# ANALOG.net
KiCad netlist of a schematic drawn in Altium Designer
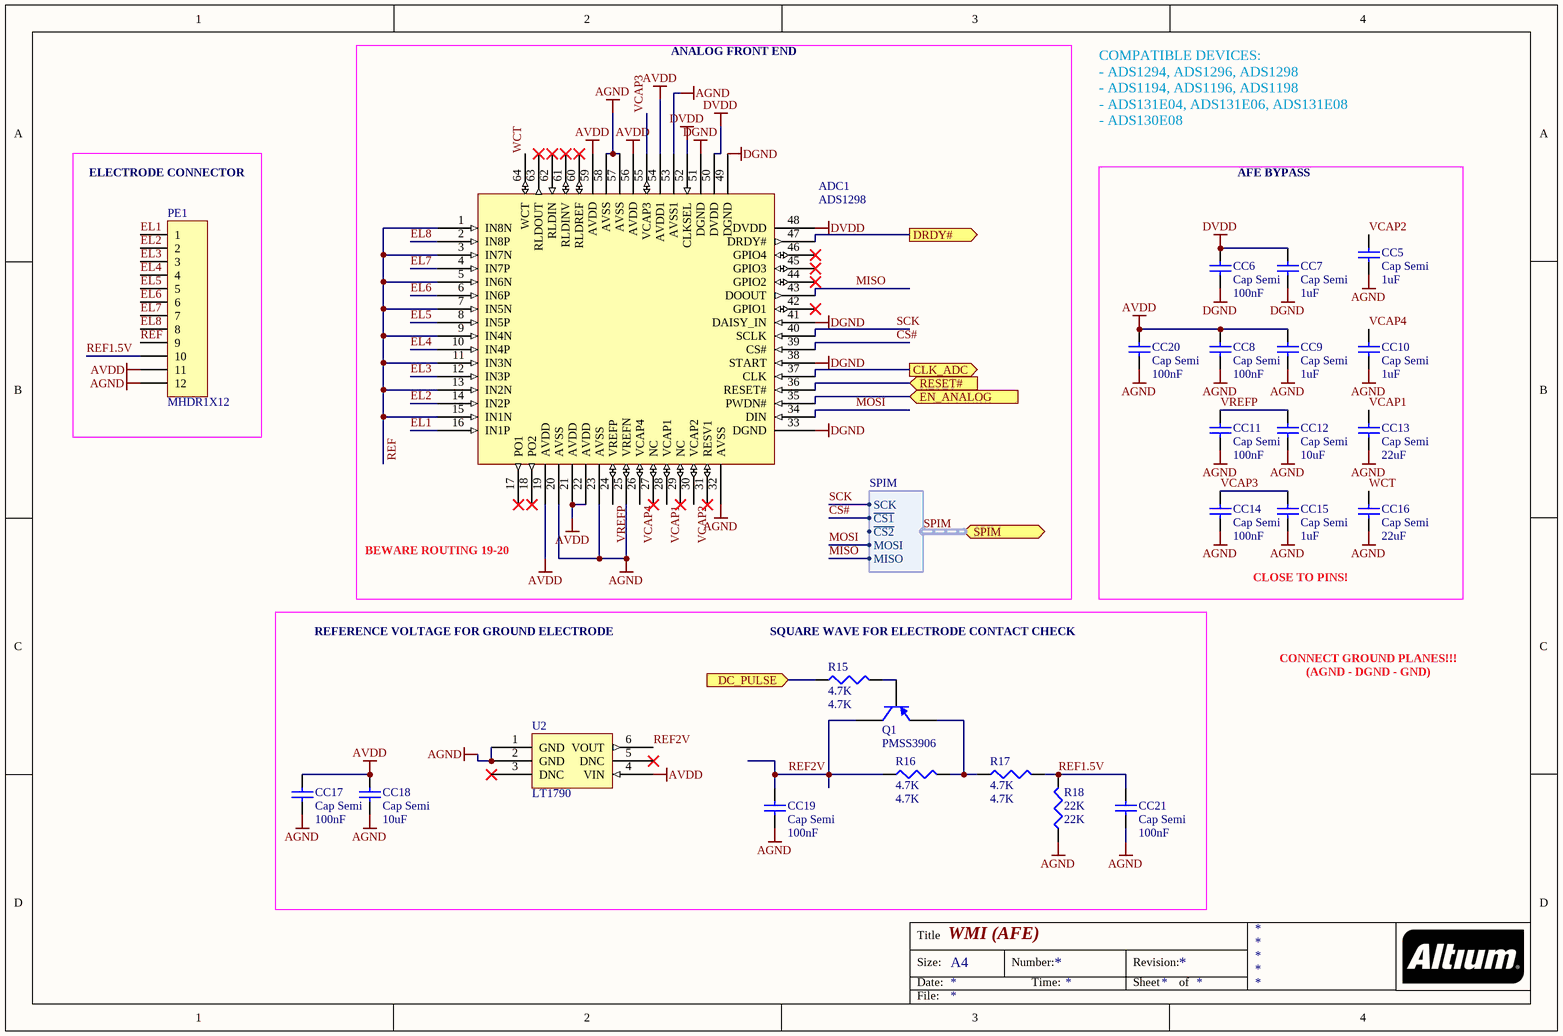
[diagram p0: ANALOG.SchDoc]

(export (version "E")
  (design (tool "Eeschema 10.0.6"))
  (components
    (comp (ref "ADC1")
      (value "ADS1298")
      (footprint "Atmel Microcontroller 32-Bit ARM:LQFP64_M")
      (libsource (lib "Schlib1") (part "ADS1298"))
    )
    (comp (ref "CC5")
      (value "Cap Semi")
      (footprint "0402")
      (description "Capacitor (Semiconductor SIM Model)")
      (fields (field (name "ALTIUM_VALUE") "1uF") (field (name "PUBLISHER") "Altium Limited"))
      (libsource (lib "Miscellaneous Devices") (part "Cap Semi"))
    )
    (comp (ref "CC6")
      (value "Cap Semi")
      (footprint "0402")
      (description "Capacitor (Semiconductor SIM Model)")
      (fields (field (name "ALTIUM_VALUE") "100nF") (field (name "PUBLISHER") "Altium Limited"))
      (libsource (lib "Miscellaneous Devices") (part "Cap Semi"))
    )
    (comp (ref "CC7")
      (value "Cap Semi")
      (footprint "0402")
      (description "Capacitor (Semiconductor SIM Model)")
      (fields (field (name "ALTIUM_VALUE") "1uF") (field (name "PUBLISHER") "Altium Limited"))
      (libsource (lib "Miscellaneous Devices") (part "Cap Semi"))
    )
    (comp (ref "CC8")
      (value "Cap Semi")
      (footprint "0402")
      (description "Capacitor (Semiconductor SIM Model)")
      (fields (field (name "ALTIUM_VALUE") "100nF") (field (name "PUBLISHER") "Altium Limited"))
      (libsource (lib "Miscellaneous Devices") (part "Cap Semi"))
    )
    (comp (ref "CC9")
      (value "Cap Semi")
      (footprint "0402")
      (description "Capacitor (Semiconductor SIM Model)")
      (fields (field (name "ALTIUM_VALUE") "1uF") (field (name "PUBLISHER") "Altium Limited"))
      (libsource (lib "Miscellaneous Devices") (part "Cap Semi"))
    )
    (comp (ref "CC10")
      (value "Cap Semi")
      (footprint "0402")
      (description "Capacitor (Semiconductor SIM Model)")
      (fields (field (name "ALTIUM_VALUE") "1uF") (field (name "PUBLISHER") "Altium Limited"))
      (libsource (lib "Miscellaneous Devices") (part "Cap Semi"))
    )
    (comp (ref "CC11")
      (value "Cap Semi")
      (footprint "0402")
      (description "Capacitor (Semiconductor SIM Model)")
      (fields (field (name "ALTIUM_VALUE") "100nF") (field (name "PUBLISHER") "Altium Limited"))
      (libsource (lib "Miscellaneous Devices") (part "Cap Semi"))
    )
    (comp (ref "CC12")
      (value "Cap Semi")
      (footprint "0402")
      (description "Capacitor (Semiconductor SIM Model)")
      (fields (field (name "ALTIUM_VALUE") "10uF") (field (name "PUBLISHER") "Altium Limited"))
      (libsource (lib "Miscellaneous Devices") (part "Cap Semi"))
    )
    (comp (ref "CC13")
      (value "Cap Semi")
      (footprint "0402")
      (description "Capacitor (Semiconductor SIM Model)")
      (fields (field (name "ALTIUM_VALUE") "22uF") (field (name "PUBLISHER") "Altium Limited"))
      (libsource (lib "Miscellaneous Devices") (part "Cap Semi"))
    )
    (comp (ref "CC14")
      (value "Cap Semi")
      (footprint "0402")
      (description "Capacitor (Semiconductor SIM Model)")
      (fields (field (name "ALTIUM_VALUE") "100nF") (field (name "PUBLISHER") "Altium Limited"))
      (libsource (lib "Miscellaneous Devices") (part "Cap Semi"))
    )
    (comp (ref "CC15")
      (value "Cap Semi")
      (footprint "0402")
      (description "Capacitor (Semiconductor SIM Model)")
      (fields (field (name "ALTIUM_VALUE") "1uF") (field (name "PUBLISHER") "Altium Limited"))
      (libsource (lib "Miscellaneous Devices") (part "Cap Semi"))
    )
    (comp (ref "CC16")
      (value "Cap Semi")
      (footprint "1608[0603]")
      (description "Capacitor (Semiconductor SIM Model)")
      (fields (field (name "ALTIUM_VALUE") "22uF") (field (name "PUBLISHER") "Altium Limited"))
      (libsource (lib "Miscellaneous Devices") (part "Cap Semi"))
    )
    (comp (ref "CC17")
      (value "Cap Semi")
      (footprint "0402")
      (description "Capacitor (Semiconductor SIM Model)")
      (fields (field (name "ALTIUM_VALUE") "100nF") (field (name "PUBLISHER") "Altium Limited"))
      (libsource (lib "Miscellaneous Devices") (part "Cap Semi"))
    )
    (comp (ref "CC18")
      (value "Cap Semi")
      (footprint "0402")
      (description "Capacitor (Semiconductor SIM Model)")
      (fields (field (name "ALTIUM_VALUE") "10uF") (field (name "PUBLISHER") "Altium Limited"))
      (libsource (lib "Miscellaneous Devices") (part "Cap Semi"))
    )
    (comp (ref "CC19")
      (value "Cap Semi")
      (footprint "0402")
      (description "Capacitor (Semiconductor SIM Model)")
      (fields (field (name "ALTIUM_VALUE") "100nF") (field (name "PUBLISHER") "Altium Limited"))
      (libsource (lib "Miscellaneous Devices") (part "Cap Semi"))
    )
    (comp (ref "CC20")
      (value "Cap Semi")
      (footprint "0402")
      (description "Capacitor (Semiconductor SIM Model)")
      (fields (field (name "ALTIUM_VALUE") "100nF") (field (name "PUBLISHER") "Altium Limited"))
      (libsource (lib "Miscellaneous Devices") (part "Cap Semi"))
    )
    (comp (ref "CC21")
      (value "Cap Semi")
      (footprint "0402")
      (description "Capacitor (Semiconductor SIM Model)")
      (fields (field (name "ALTIUM_VALUE") "100nF") (field (name "PUBLISHER") "Altium Limited"))
      (libsource (lib "Miscellaneous Devices") (part "Cap Semi"))
    )
    (comp (ref "PE1")
      (value "MHDR1X12")
      (footprint "HEADER12")
      (description "Header, 12-Pin")
      (fields (field (name "PUBLISHER") "Altium Limited"))
      (libsource (lib "Miscellaneous Connectors") (part "MHDR1X12"))
    )
    (comp (ref "Q1")
      (value "PMSS3906")
      (footprint "SOT323_N")
      (description "PNP Switching Transistor")
      (fields (field (name "PUBLISHER") "Altium Limited"))
      (libsource (lib "Philips Discrete BJT - Low Power") (part "PMSS3906"))
    )
    (comp (ref "R15")
      (value "4.7K")
      (footprint "0402")
      (description "Resistor")
      (fields (field (name "ALTIUM_VALUE") "4.7K") (field (name "PUBLISHER") "Altium Limited"))
      (libsource (lib "Miscellaneous Devices") (part "Res3"))
    )
    (comp (ref "R16")
      (value "4.7K")
      (footprint "0402")
      (description "Resistor")
      (fields (field (name "ALTIUM_VALUE") "4.7K") (field (name "PUBLISHER") "Altium Limited"))
      (libsource (lib "Miscellaneous Devices") (part "Res3"))
    )
    (comp (ref "R17")
      (value "4.7K")
      (footprint "0402")
      (description "Resistor")
      (fields (field (name "ALTIUM_VALUE") "4.7K") (field (name "PUBLISHER") "Altium Limited"))
      (libsource (lib "Miscellaneous Devices") (part "Res3"))
    )
    (comp (ref "R18")
      (value "22K")
      (footprint "0402")
      (description "Resistor")
      (fields (field (name "ALTIUM_VALUE") "22K") (field (name "PUBLISHER") "Altium Limited"))
      (libsource (lib "Miscellaneous Devices") (part "Res3"))
    )
    (comp (ref "U2") (value "LT1790") (footprint "SOT-23_A_N") (libsource (lib "Schlib1") (part "LT1790")))
  )
  (nets
    (net (code "2") (name "/CLK_ADC") (class "Default")
      (node (ref "ADC1") (pin "37") (pinfunction "CLK_37") (pintype "input"))
    )
    (net (code "3") (name "/CS#") (class "Default")
      (node (ref "ADC1") (pin "39") (pinfunction "CS#_39") (pintype "input"))
    )
    (net (code "4") (name "/DC_PULSE") (class "Default")
      (node (ref "R15") (pin "1") (pinfunction "1_1") (pintype "passive"))
    )
    (net (code "5") (name "/DRDY#") (class "Default")
      (node (ref "ADC1") (pin "47") (pinfunction "DRDY#_47") (pintype "output"))
    )
    (net (code "6") (name "/EL1") (class "Default")
      (node (ref "ADC1") (pin "16") (pinfunction "IN1P_16") (pintype "input"))
      (node (ref "PE1") (pin "1") (pinfunction "1_1") (pintype "passive"))
    )
    (net (code "7") (name "/EL2") (class "Default")
      (node (ref "ADC1") (pin "14") (pinfunction "IN2P_14") (pintype "input"))
      (node (ref "PE1") (pin "2") (pinfunction "2_2") (pintype "passive"))
    )
    (net (code "8") (name "/EL3") (class "Default")
      (node (ref "ADC1") (pin "12") (pinfunction "IN3P_12") (pintype "input"))
      (node (ref "PE1") (pin "3") (pinfunction "3_3") (pintype "passive"))
    )
    (net (code "9") (name "/EL4") (class "Default")
      (node (ref "ADC1") (pin "10") (pinfunction "IN4P_10") (pintype "input"))
      (node (ref "PE1") (pin "4") (pinfunction "4_4") (pintype "passive"))
    )
    (net (code "10") (name "/EL5") (class "Default")
      (node (ref "ADC1") (pin "8") (pinfunction "IN5P_8") (pintype "input"))
      (node (ref "PE1") (pin "5") (pinfunction "5_5") (pintype "passive"))
    )
    (net (code "11") (name "/EL6") (class "Default")
      (node (ref "ADC1") (pin "6") (pinfunction "IN6P_6") (pintype "input"))
      (node (ref "PE1") (pin "6") (pinfunction "6_6") (pintype "passive"))
    )
    (net (code "12") (name "/EL7") (class "Default")
      (node (ref "ADC1") (pin "4") (pinfunction "IN7P_4") (pintype "input"))
      (node (ref "PE1") (pin "7") (pinfunction "7_7") (pintype "passive"))
    )
    (net (code "13") (name "/EL8") (class "Default")
      (node (ref "ADC1") (pin "2") (pinfunction "IN8P_2") (pintype "input"))
      (node (ref "PE1") (pin "8") (pinfunction "8_8") (pintype "passive"))
    )
    (net (code "14") (name "/EN_ANALOG") (class "Default")
      (node (ref "ADC1") (pin "35") (pinfunction "PWDN#_35") (pintype "input"))
    )
    (net (code "15") (name "/MISO") (class "Default")
      (node (ref "ADC1") (pin "43") (pinfunction "DOOUT_43") (pintype "output"))
    )
    (net (code "16") (name "/MOSI") (class "Default")
      (node (ref "ADC1") (pin "34") (pinfunction "DIN_34") (pintype "input"))
    )
    (net (code "17") (name "/REF") (class "Default")
      (node (ref "ADC1") (pin "1") (pinfunction "IN8N_1") (pintype "input"))
      (node (ref "ADC1") (pin "11") (pinfunction "IN3N_11") (pintype "input"))
      (node (ref "ADC1") (pin "13") (pinfunction "IN2N_13") (pintype "input"))
      (node (ref "ADC1") (pin "15") (pinfunction "IN1N_15") (pintype "input"))
      (node (ref "ADC1") (pin "3") (pinfunction "IN7N_3") (pintype "input"))
      (node (ref "ADC1") (pin "5") (pinfunction "IN6N_5") (pintype "input"))
      (node (ref "ADC1") (pin "7") (pinfunction "IN5N_7") (pintype "input"))
      (node (ref "ADC1") (pin "9") (pinfunction "IN4N_9") (pintype "input"))
      (node (ref "PE1") (pin "9") (pinfunction "9_9") (pintype "passive"))
    )
    (net (code "18") (name "/REF1.5V") (class "Default")
      (node (ref "CC21") (pin "2") (pinfunction "2_2") (pintype "passive"))
      (node (ref "PE1") (pin "10") (pinfunction "10_10") (pintype "passive"))
      (node (ref "R17") (pin "2") (pinfunction "2_2") (pintype "passive"))
      (node (ref "R18") (pin "2") (pinfunction "2_2") (pintype "passive"))
    )
    (net (code "19") (name "/REF2V") (class "Default")
      (node (ref "CC19") (pin "2") (pinfunction "2_2") (pintype "passive"))
      (node (ref "Q1") (pin "3") (pinfunction "C_3") (pintype "passive"))
      (node (ref "R16") (pin "1") (pinfunction "1_1") (pintype "passive"))
      (node (ref "U2") (pin "6") (pinfunction "VOUT_6") (pintype "output"))
    )
    (net (code "20") (name "/RESET#") (class "Default")
      (node (ref "ADC1") (pin "36") (pinfunction "RESET#_36") (pintype "input"))
    )
    (net (code "21") (name "/SCK") (class "Default")
      (node (ref "ADC1") (pin "40") (pinfunction "SCLK_40") (pintype "input"))
    )
    (net (code "23") (name "/VCAP1") (class "Default")
      (node (ref "ADC1") (pin "28") (pinfunction "VCAP1_28") (pintype "bidirectional"))
      (node (ref "CC13") (pin "2") (pinfunction "2_2") (pintype "passive"))
    )
    (net (code "24") (name "/VCAP2") (class "Default")
      (node (ref "ADC1") (pin "30") (pinfunction "VCAP2_30") (pintype "bidirectional"))
      (node (ref "CC5") (pin "2") (pinfunction "2_2") (pintype "passive"))
    )
    (net (code "25") (name "/VCAP3") (class "Default")
      (node (ref "ADC1") (pin "55") (pinfunction "VCAP3_55") (pintype "bidirectional"))
      (node (ref "CC14") (pin "2") (pinfunction "2_2") (pintype "passive"))
      (node (ref "CC15") (pin "2") (pinfunction "2_2") (pintype "passive"))
    )
    (net (code "26") (name "/VCAP4") (class "Default")
      (node (ref "ADC1") (pin "26") (pinfunction "VCAP4_26") (pintype "bidirectional"))
      (node (ref "CC10") (pin "2") (pinfunction "2_2") (pintype "passive"))
    )
    (net (code "27") (name "/VREFP") (class "Default")
      (node (ref "ADC1") (pin "24") (pinfunction "VREFP_24") (pintype "bidirectional"))
      (node (ref "CC11") (pin "2") (pinfunction "2_2") (pintype "passive"))
      (node (ref "CC12") (pin "2") (pinfunction "2_2") (pintype "passive"))
    )
    (net (code "28") (name "/WCT") (class "Default")
      (node (ref "ADC1") (pin "64") (pinfunction "WCT_64") (pintype "bidirectional"))
      (node (ref "CC16") (pin "2") (pinfunction "2_2") (pintype "passive"))
    )
    (net (code "29") (name "AGND") (class "Default")
      (node (ref "ADC1") (pin "20") (pinfunction "AVSS_20") (pintype "power_in"))
      (node (ref "ADC1") (pin "23") (pinfunction "AVSS_23") (pintype "power_in"))
      (node (ref "ADC1") (pin "25") (pinfunction "VREFN_25") (pintype "bidirectional"))
      (node (ref "ADC1") (pin "32") (pinfunction "AVSS_32") (pintype "power_in"))
      (node (ref "ADC1") (pin "53") (pinfunction "AVSS1_53") (pintype "power_in"))
      (node (ref "ADC1") (pin "57") (pinfunction "AVSS_57") (pintype "power_in"))
      (node (ref "ADC1") (pin "58") (pinfunction "AVSS_58") (pintype "power_in"))
      (node (ref "CC10") (pin "1") (pinfunction "1_1") (pintype "passive"))
      (node (ref "CC11") (pin "1") (pinfunction "1_1") (pintype "passive"))
      (node (ref "CC12") (pin "1") (pinfunction "1_1") (pintype "passive"))
      (node (ref "CC13") (pin "1") (pinfunction "1_1") (pintype "passive"))
      (node (ref "CC14") (pin "1") (pinfunction "1_1") (pintype "passive"))
      (node (ref "CC15") (pin "1") (pinfunction "1_1") (pintype "passive"))
      (node (ref "CC16") (pin "1") (pinfunction "1_1") (pintype "passive"))
      (node (ref "CC17") (pin "1") (pinfunction "1_1") (pintype "passive"))
      (node (ref "CC18") (pin "1") (pinfunction "1_1") (pintype "passive"))
      (node (ref "CC19") (pin "1") (pinfunction "1_1") (pintype "passive"))
      (node (ref "CC20") (pin "1") (pinfunction "1_1") (pintype "passive"))
      (node (ref "CC21") (pin "1") (pinfunction "1_1") (pintype "passive"))
      (node (ref "CC5") (pin "1") (pinfunction "1_1") (pintype "passive"))
      (node (ref "CC8") (pin "1") (pinfunction "1_1") (pintype "passive"))
      (node (ref "CC9") (pin "1") (pinfunction "1_1") (pintype "passive"))
      (node (ref "PE1") (pin "12") (pinfunction "12_12") (pintype "passive"))
      (node (ref "R18") (pin "1") (pinfunction "1_1") (pintype "passive"))
      (node (ref "U2") (pin "1") (pinfunction "GND_1") (pintype "power_in"))
      (node (ref "U2") (pin "2") (pinfunction "GND_2") (pintype "power_in"))
    )
    (net (code "30") (name "AVDD") (class "Default")
      (node (ref "ADC1") (pin "19") (pinfunction "AVDD_19") (pintype "power_in"))
      (node (ref "ADC1") (pin "21") (pinfunction "AVDD_21") (pintype "power_in"))
      (node (ref "ADC1") (pin "22") (pinfunction "AVDD_22") (pintype "power_in"))
      (node (ref "ADC1") (pin "54") (pinfunction "AVDD1_54") (pintype "power_in"))
      (node (ref "ADC1") (pin "56") (pinfunction "AVDD_56") (pintype "power_in"))
      (node (ref "ADC1") (pin "59") (pinfunction "AVDD_59") (pintype "power_in"))
      (node (ref "CC17") (pin "2") (pinfunction "2_2") (pintype "passive"))
      (node (ref "CC18") (pin "2") (pinfunction "2_2") (pintype "passive"))
      (node (ref "CC20") (pin "2") (pinfunction "2_2") (pintype "passive"))
      (node (ref "CC8") (pin "2") (pinfunction "2_2") (pintype "passive"))
      (node (ref "CC9") (pin "2") (pinfunction "2_2") (pintype "passive"))
      (node (ref "PE1") (pin "11") (pinfunction "11_11") (pintype "passive"))
      (node (ref "U2") (pin "4") (pinfunction "VIN_4") (pintype "input"))
    )
    (net (code "31") (name "DGND") (class "Default")
      (node (ref "ADC1") (pin "33") (pinfunction "DGND_33") (pintype "power_in"))
      (node (ref "ADC1") (pin "38") (pinfunction "START_38") (pintype "input"))
      (node (ref "ADC1") (pin "41") (pinfunction "DAISY_IN_41") (pintype "input"))
      (node (ref "ADC1") (pin "49") (pinfunction "DGND_49") (pintype "power_in"))
      (node (ref "ADC1") (pin "51") (pinfunction "DGND_51") (pintype "power_in"))
      (node (ref "CC6") (pin "1") (pinfunction "1_1") (pintype "passive"))
      (node (ref "CC7") (pin "1") (pinfunction "1_1") (pintype "passive"))
    )
    (net (code "32") (name "DVDD") (class "Default")
      (node (ref "ADC1") (pin "48") (pinfunction "DVDD_48") (pintype "power_in"))
      (node (ref "ADC1") (pin "50") (pinfunction "DVDD_50") (pintype "power_in"))
      (node (ref "ADC1") (pin "52") (pinfunction "CLKSEL_52") (pintype "input"))
      (node (ref "CC6") (pin "2") (pinfunction "2_2") (pintype "passive"))
      (node (ref "CC7") (pin "2") (pinfunction "2_2") (pintype "passive"))
    )
    (net (code "33") (name "Net-(Q1-B)") (class "Default")
      (node (ref "Q1") (pin "1") (pinfunction "B_1") (pintype "passive"))
      (node (ref "R15") (pin "2") (pinfunction "2_2") (pintype "passive"))
    )
    (net (code "34") (name "Net-(Q1-E)") (class "Default")
      (node (ref "Q1") (pin "2") (pinfunction "E_2") (pintype "passive"))
      (node (ref "R16") (pin "2") (pinfunction "2_2") (pintype "passive"))
      (node (ref "R17") (pin "1") (pinfunction "1_1") (pintype "passive"))
    )
    (net (code "35") (name "unconnected-(ADC1-GPIO1-Pad42)") (class "Default")
      (node (ref "ADC1") (pin "42") (pinfunction "GPIO1_42") (pintype "bidirectional+no_connect"))
    )
    (net (code "36") (name "unconnected-(ADC1-GPIO2-Pad44)") (class "Default")
      (node (ref "ADC1") (pin "44") (pinfunction "GPIO2_44") (pintype "bidirectional+no_connect"))
    )
    (net (code "37") (name "unconnected-(ADC1-GPIO3-Pad45)") (class "Default")
      (node (ref "ADC1") (pin "45") (pinfunction "GPIO3_45") (pintype "bidirectional+no_connect"))
    )
    (net (code "38") (name "unconnected-(ADC1-GPIO4-Pad46)") (class "Default")
      (node (ref "ADC1") (pin "46") (pinfunction "GPIO4_46") (pintype "bidirectional+no_connect"))
    )
    (net (code "39") (name "unconnected-(ADC1-NC-Pad27)") (class "Default")
      (node (ref "ADC1") (pin "27") (pinfunction "NC_27") (pintype "bidirectional+no_connect"))
    )
    (net (code "40") (name "unconnected-(ADC1-NC-Pad29)") (class "Default")
      (node (ref "ADC1") (pin "29") (pinfunction "NC_29") (pintype "bidirectional+no_connect"))
    )
    (net (code "41") (name "unconnected-(ADC1-PO1-Pad17)") (class "Default")
      (node (ref "ADC1") (pin "17") (pinfunction "PO1_17") (pintype "output+no_connect"))
    )
    (net (code "42") (name "unconnected-(ADC1-PO2-Pad18)") (class "Default")
      (node (ref "ADC1") (pin "18") (pinfunction "PO2_18") (pintype "output+no_connect"))
    )
    (net (code "43") (name "unconnected-(ADC1-RESV1-Pad31)") (class "Default")
      (node (ref "ADC1") (pin "31") (pinfunction "RESV1_31") (pintype "bidirectional+no_connect"))
    )
    (net (code "44") (name "unconnected-(ADC1-RLDIN-Pad62)") (class "Default")
      (node (ref "ADC1") (pin "62") (pinfunction "RLDIN_62") (pintype "input+no_connect"))
    )
    (net (code "45") (name "unconnected-(ADC1-RLDINV-Pad61)") (class "Default")
      (node (ref "ADC1") (pin "61") (pinfunction "RLDINV_61") (pintype "bidirectional+no_connect"))
    )
    (net (code "46") (name "unconnected-(ADC1-RLDOUT-Pad63)") (class "Default")
      (node (ref "ADC1") (pin "63") (pinfunction "RLDOUT_63") (pintype "output+no_connect"))
    )
    (net (code "47") (name "unconnected-(ADC1-RLDREF-Pad60)") (class "Default")
      (node (ref "ADC1") (pin "60") (pinfunction "RLDREF_60") (pintype "bidirectional+no_connect"))
    )
    (net (code "48") (name "unconnected-(U2-DNC-Pad3)") (class "Default")
      (node (ref "U2") (pin "3") (pinfunction "DNC_3") (pintype "passive+no_connect"))
    )
    (net (code "49") (name "unconnected-(U2-DNC-Pad5)") (class "Default")
      (node (ref "U2") (pin "5") (pinfunction "DNC_5") (pintype "passive+no_connect"))
    )
  )
)
